# Main.net
KiCad netlist of a schematic drawn in Altium Designer
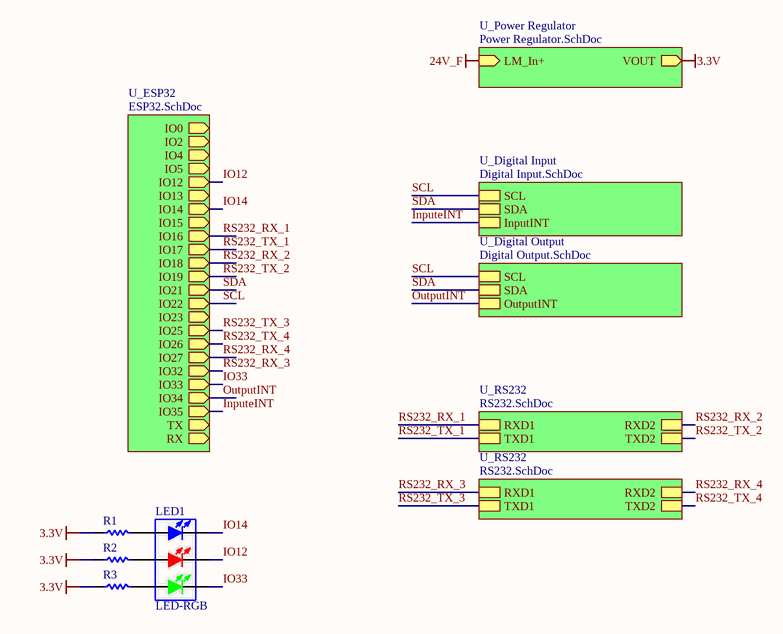
[diagram p0: Main.SchDoc]

(export (version "E")
  (design (tool "Eeschema 10.0.6"))
  (components
    (comp (ref "LED1")
      (value "LED-RGB")
      (footprint "LED 3535")
      (description "Three primary color LED")
      (fields (field (name "版权归属") "源创客"))
      (libsource (lib "LED") (part "LED-RGB"))
    )
    (comp (ref "R1")
      (value "1K")
      (footprint "R 0805")
      (description "Chip resistor")
      (fields (field (name "版权归属") "源创客"))
      (libsource (lib "Passive (Resistor-Capacitor-Inductor-Veristor-Ferrite)") (part "R"))
    )
    (comp (ref "R2")
      (value "1K")
      (footprint "R 0805")
      (description "Chip resistor")
      (fields (field (name "版权归属") "源创客"))
      (libsource (lib "Passive (Resistor-Capacitor-Inductor-Veristor-Ferrite)") (part "R"))
    )
    (comp (ref "R3")
      (value "1K")
      (footprint "R 0805")
      (description "Chip resistor")
      (fields (field (name "版权归属") "源创客"))
      (libsource (lib "Passive (Resistor-Capacitor-Inductor-Veristor-Ferrite)") (part "R"))
    )
  )
  (nets
    (net (code "5") (name "/IO12") (class "Default")
      (node (ref "LED1") (pin "5") (pinfunction "RED_K_5") (pintype "passive"))
    )
    (net (code "7") (name "/IO14") (class "Default")
      (node (ref "LED1") (pin "6") (pinfunction "BULE_K_6") (pintype "passive"))
    )
    (net (code "10") (name "/IO33") (class "Default")
      (node (ref "LED1") (pin "4") (pinfunction "GREEN_K_4") (pintype "passive"))
    )
    (net (code "25") (name "3.3V") (class "Default")
      (node (ref "R1") (pin "1") (pinfunction "1_1") (pintype "passive"))
      (node (ref "R2") (pin "1") (pinfunction "1_1") (pintype "passive"))
      (node (ref "R3") (pin "1") (pinfunction "1_1") (pintype "passive"))
    )
    (net (code "27") (name "Net-(LED1-BULE_A)") (class "Default")
      (node (ref "LED1") (pin "1") (pinfunction "BULE_A_1") (pintype "passive"))
      (node (ref "R1") (pin "2") (pinfunction "2_2") (pintype "passive"))
    )
    (net (code "28") (name "Net-(LED1-GREEN_A)") (class "Default")
      (node (ref "LED1") (pin "3") (pinfunction "GREEN_A_3") (pintype "passive"))
      (node (ref "R3") (pin "2") (pinfunction "2_2") (pintype "passive"))
    )
    (net (code "29") (name "Net-(LED1-RED_A)") (class "Default")
      (node (ref "LED1") (pin "2") (pinfunction "RED_A_2") (pintype "passive"))
      (node (ref "R2") (pin "2") (pinfunction "2_2") (pintype "passive"))
    )
  )
)
